# M705X.net
KiCad netlist of a schematic drawn in EAGLE
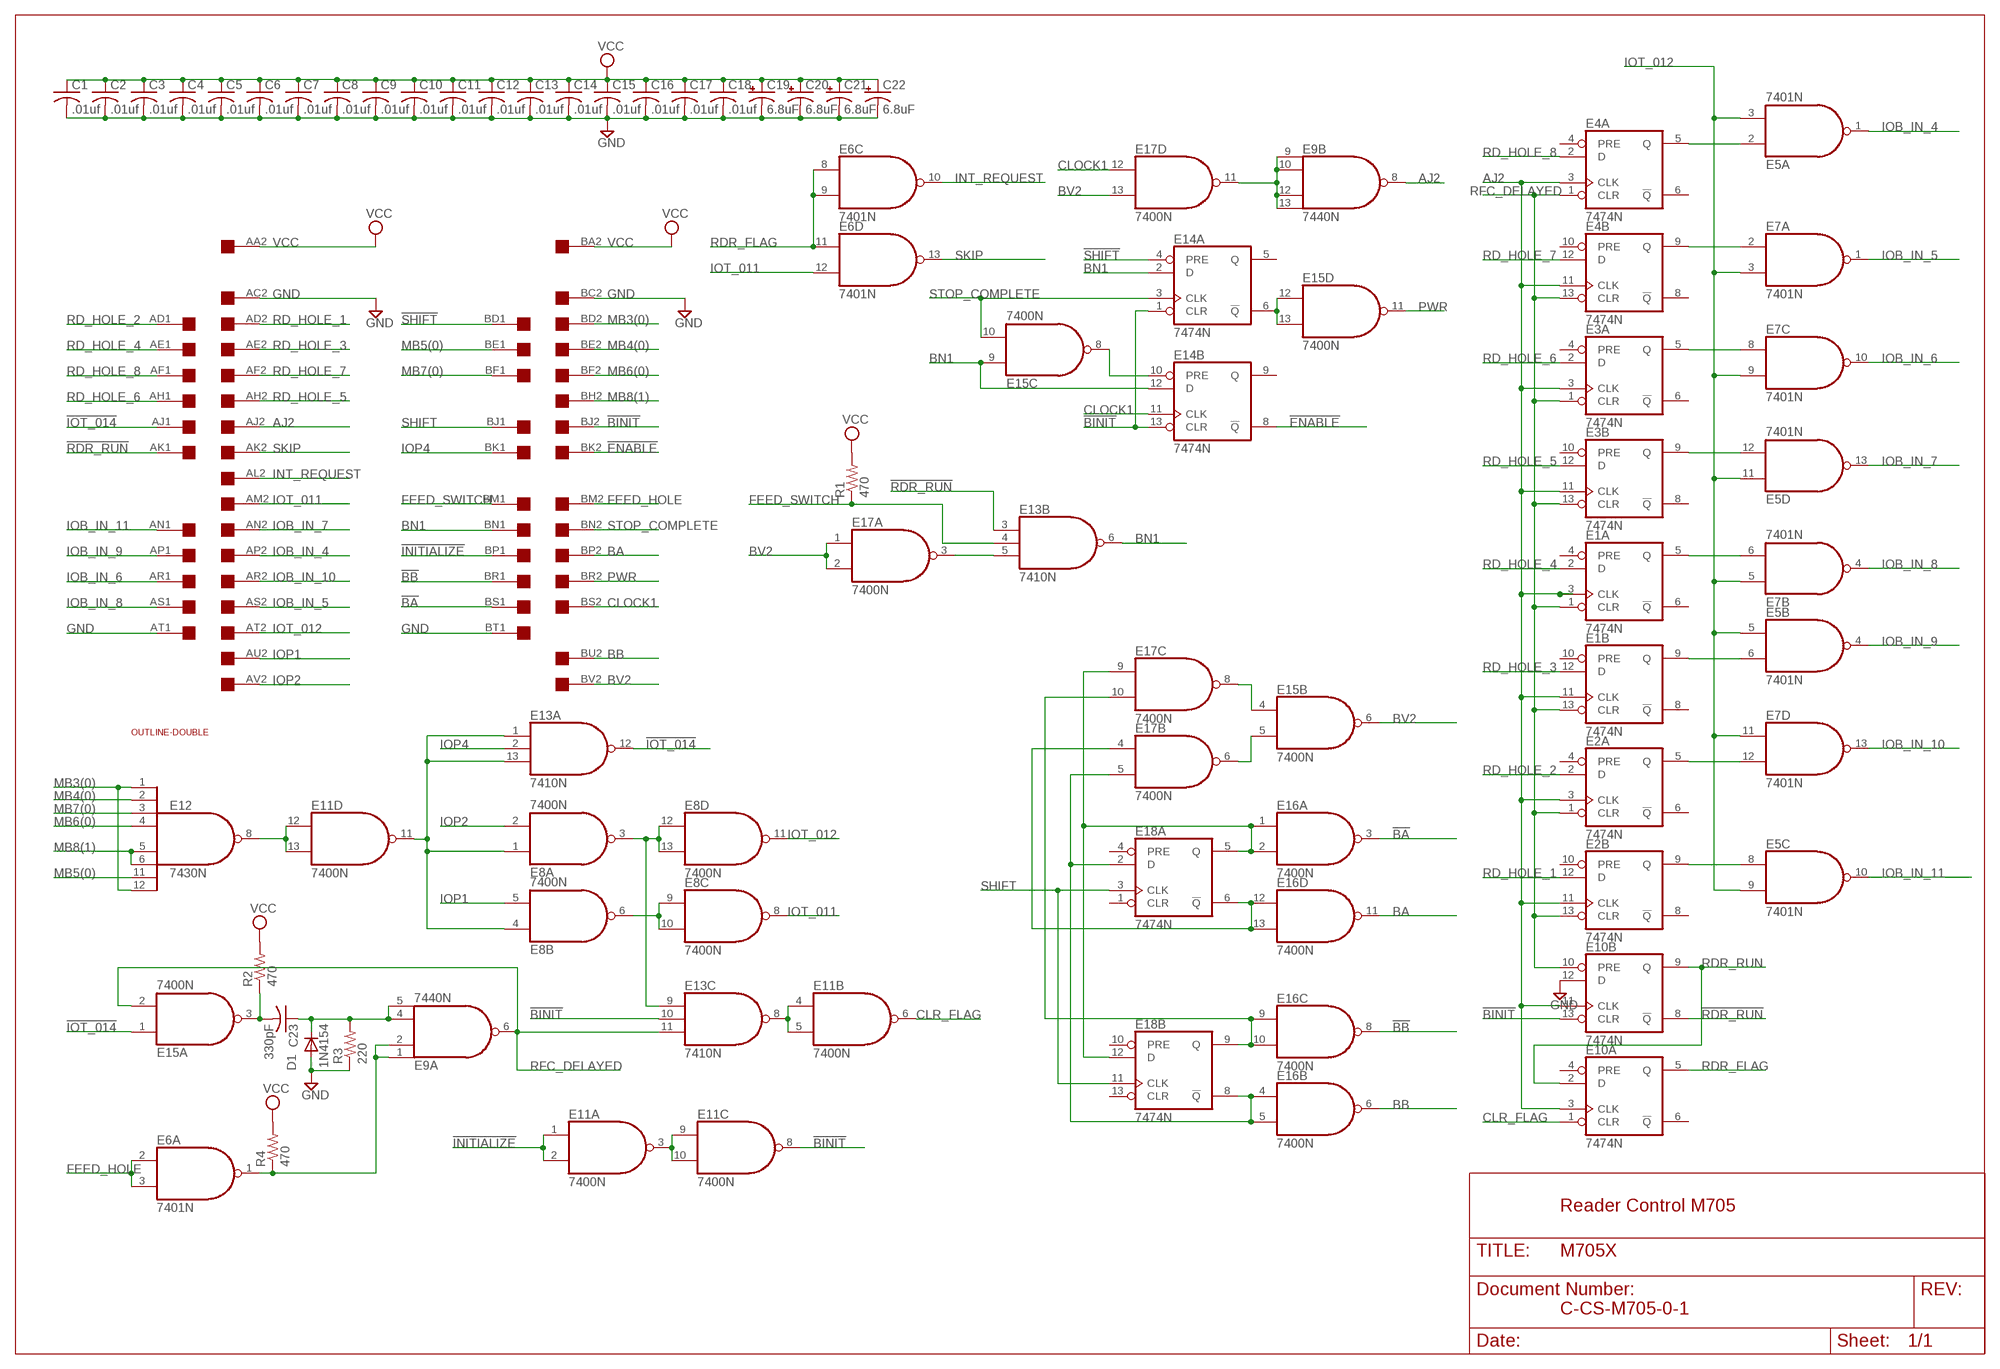
[diagram p0: schematic, sheet 1]

(export (version "E")
  (design (tool "Eeschema 10.0.6"))
  (components
    (comp (ref "C1")
      (value ".01uf")
      (footprint "eagle-import:C075-032X103")
      (libsource (lib "eagle-import") (part "C-US075-032X103"))
    )
    (comp (ref "C2")
      (value ".01uf")
      (footprint "eagle-import:C075-032X103")
      (libsource (lib "eagle-import") (part "C-US075-032X103"))
    )
    (comp (ref "C3")
      (value ".01uf")
      (footprint "eagle-import:C075-032X103")
      (libsource (lib "eagle-import") (part "C-US075-032X103"))
    )
    (comp (ref "C4")
      (value ".01uf")
      (footprint "eagle-import:C075-032X103")
      (libsource (lib "eagle-import") (part "C-US075-032X103"))
    )
    (comp (ref "C5")
      (value ".01uf")
      (footprint "eagle-import:C075-032X103")
      (libsource (lib "eagle-import") (part "C-US075-032X103"))
    )
    (comp (ref "C6")
      (value ".01uf")
      (footprint "eagle-import:C075-032X103")
      (libsource (lib "eagle-import") (part "C-US075-032X103"))
    )
    (comp (ref "C7")
      (value ".01uf")
      (footprint "eagle-import:C075-032X103")
      (libsource (lib "eagle-import") (part "C-US075-032X103"))
    )
    (comp (ref "C8")
      (value ".01uf")
      (footprint "eagle-import:C075-032X103")
      (libsource (lib "eagle-import") (part "C-US075-032X103"))
    )
    (comp (ref "C9")
      (value ".01uf")
      (footprint "eagle-import:C075-032X103")
      (libsource (lib "eagle-import") (part "C-US075-032X103"))
    )
    (comp (ref "C10")
      (value ".01uf")
      (footprint "eagle-import:C075-032X103")
      (libsource (lib "eagle-import") (part "C-US075-032X103"))
    )
    (comp (ref "C11")
      (value ".01uf")
      (footprint "eagle-import:C075-032X103")
      (libsource (lib "eagle-import") (part "C-US075-032X103"))
    )
    (comp (ref "C12")
      (value ".01uf")
      (footprint "eagle-import:C075-032X103")
      (libsource (lib "eagle-import") (part "C-US075-032X103"))
    )
    (comp (ref "C13")
      (value ".01uf")
      (footprint "eagle-import:C075-032X103")
      (libsource (lib "eagle-import") (part "C-US075-032X103"))
    )
    (comp (ref "C14")
      (value ".01uf")
      (footprint "eagle-import:C075-032X103")
      (libsource (lib "eagle-import") (part "C-US075-032X103"))
    )
    (comp (ref "C15")
      (value ".01uf")
      (footprint "eagle-import:C075-032X103")
      (libsource (lib "eagle-import") (part "C-US075-032X103"))
    )
    (comp (ref "C16")
      (value ".01uf")
      (footprint "eagle-import:C075-032X103")
      (libsource (lib "eagle-import") (part "C-US075-032X103"))
    )
    (comp (ref "C17")
      (value ".01uf")
      (footprint "eagle-import:C075-032X103")
      (libsource (lib "eagle-import") (part "C-US075-032X103"))
    )
    (comp (ref "C18")
      (value ".01uf")
      (footprint "eagle-import:C075-032X103")
      (libsource (lib "eagle-import") (part "C-US075-032X103"))
    )
    (comp (ref "C19")
      (value "6.8uF")
      (footprint "eagle-import:E12-8")
      (libsource (lib "eagle-import") (part "CPOL-USE20-8AXIAL"))
    )
    (comp (ref "C20")
      (value "6.8uF")
      (footprint "eagle-import:E12-8")
      (libsource (lib "eagle-import") (part "CPOL-USE20-8AXIAL"))
    )
    (comp (ref "C21")
      (value "6.8uF")
      (footprint "eagle-import:E12-8")
      (libsource (lib "eagle-import") (part "CPOL-USE20-8AXIAL"))
    )
    (comp (ref "C22")
      (value "6.8uF")
      (footprint "eagle-import:E12-8")
      (libsource (lib "eagle-import") (part "CPOL-USE20-8AXIAL"))
    )
    (comp (ref "C23")
      (value "330pF")
      (footprint "eagle-import:C075-032X103")
      (libsource (lib "eagle-import") (part "C-US075-032X103"))
    )
    (comp (ref "D1")
      (value "1N4154")
      (footprint "eagle-import:DO35-10")
      (libsource (lib "eagle-import") (part "1N4148DO35-10"))
    )
    (comp (ref "E1")
      (value "7474N")
      (footprint "eagle-import:DIL14")
      (libsource (lib "eagle-import") (part "7474NS"))
    )
    (comp (ref "E2")
      (value "7474N")
      (footprint "eagle-import:DIL14")
      (libsource (lib "eagle-import") (part "7474NS"))
    )
    (comp (ref "E3")
      (value "7474N")
      (footprint "eagle-import:DIL14")
      (libsource (lib "eagle-import") (part "7474NS"))
    )
    (comp (ref "E4")
      (value "7474N")
      (footprint "eagle-import:DIL14")
      (libsource (lib "eagle-import") (part "7474NS"))
    )
    (comp (ref "E5")
      (value "7401N")
      (footprint "eagle-import:DIL14")
      (libsource (lib "eagle-import") (part "7401NLS"))
    )
    (comp (ref "E6")
      (value "7401N")
      (footprint "eagle-import:DIL14")
      (libsource (lib "eagle-import") (part "7401NLS"))
    )
    (comp (ref "E7")
      (value "7401N")
      (footprint "eagle-import:DIL14")
      (libsource (lib "eagle-import") (part "7401NLS"))
    )
    (comp (ref "E8")
      (value "7400N")
      (footprint "eagle-import:DIL14")
      (libsource (lib "eagle-import") (part "7400N"))
    )
    (comp (ref "E9")
      (value "7440N")
      (footprint "eagle-import:DIL14")
      (libsource (lib "eagle-import") (part "7420NS"))
    )
    (comp (ref "E10")
      (value "7474N")
      (footprint "eagle-import:DIL14")
      (libsource (lib "eagle-import") (part "7474NS"))
    )
    (comp (ref "E11")
      (value "7400N")
      (footprint "eagle-import:DIL14")
      (libsource (lib "eagle-import") (part "7400N"))
    )
    (comp (ref "E12")
      (value "7430N")
      (footprint "eagle-import:DIL14")
      (libsource (lib "eagle-import") (part "7430N"))
    )
    (comp (ref "E13")
      (value "7410N")
      (footprint "eagle-import:DIL14")
      (libsource (lib "eagle-import") (part "7410N"))
    )
    (comp (ref "E14")
      (value "7474N")
      (footprint "eagle-import:DIL14")
      (libsource (lib "eagle-import") (part "7474NS"))
    )
    (comp (ref "E15")
      (value "7400N")
      (footprint "eagle-import:DIL14")
      (libsource (lib "eagle-import") (part "7400N"))
    )
    (comp (ref "E16")
      (value "7400N")
      (footprint "eagle-import:DIL14")
      (libsource (lib "eagle-import") (part "7400N"))
    )
    (comp (ref "E17")
      (value "7400N")
      (footprint "eagle-import:DIL14")
      (libsource (lib "eagle-import") (part "7400N"))
    )
    (comp (ref "E18")
      (value "7474N")
      (footprint "eagle-import:DIL14")
      (libsource (lib "eagle-import") (part "7474NS"))
    )
    (comp (ref "R1")
      (value "470")
      (footprint "eagle-import:0207_10")
      (libsource (lib "eagle-import") (part "R-US_0207/10"))
    )
    (comp (ref "R2")
      (value "470")
      (footprint "eagle-import:0207_10")
      (libsource (lib "eagle-import") (part "R-US_0207/10"))
    )
    (comp (ref "R3")
      (value "220")
      (footprint "eagle-import:0207_10")
      (libsource (lib "eagle-import") (part "R-US_0207/10"))
    )
    (comp (ref "R4")
      (value "470")
      (footprint "eagle-import:0207_10")
      (libsource (lib "eagle-import") (part "R-US_0207/10"))
    )
    (comp (ref "U$5")
      (value "DOUBLE")
      (footprint "eagle-import:EDGE-CON4")
      (libsource (lib "eagle-import") (part "DOUBLE"))
    )
    (comp (ref "U$6")
      (value "OUTLINE-DOUBLE")
      (footprint "eagle-import:DOUBLE")
      (libsource (lib "eagle-import") (part "OUTLINE-DOUBLE"))
    )
  )
  (nets
    (net (code "1") (name "/AJ2") (class "Default")
      (node (ref "E1") (pin "11") (pinfunction "CLK_11") (pintype "input"))
      (node (ref "E1") (pin "3") (pinfunction "CLK_3") (pintype "input"))
      (node (ref "E10") (pin "11") (pinfunction "CLK_11") (pintype "input"))
      (node (ref "E10") (pin "3") (pinfunction "CLK_3") (pintype "input"))
      (node (ref "E2") (pin "11") (pinfunction "CLK_11") (pintype "input"))
      (node (ref "E2") (pin "3") (pinfunction "CLK_3") (pintype "input"))
      (node (ref "E3") (pin "11") (pinfunction "CLK_11") (pintype "input"))
      (node (ref "E3") (pin "3") (pinfunction "CLK_3") (pintype "input"))
      (node (ref "E4") (pin "11") (pinfunction "CLK_11") (pintype "input"))
      (node (ref "E4") (pin "3") (pinfunction "CLK_3") (pintype "input"))
      (node (ref "E9") (pin "8") (pinfunction "O_8") (pintype "output"))
      (node (ref "U$5") (pin "AJ2") (pinfunction "1_AJ2") (pintype "bidirectional"))
    )
    (net (code "2") (name "/BA") (class "Default")
      (node (ref "E16") (pin "11") (pinfunction "O_11") (pintype "output"))
      (node (ref "U$5") (pin "BP2") (pinfunction "1_BP2") (pintype "bidirectional"))
    )
    (net (code "3") (name "/BB") (class "Default")
      (node (ref "E16") (pin "6") (pinfunction "O_6") (pintype "output"))
      (node (ref "U$5") (pin "BU2") (pinfunction "1_BU2") (pintype "bidirectional"))
    )
    (net (code "4") (name "/BN1") (class "Default")
      (node (ref "E13") (pin "6") (pinfunction "O_6") (pintype "output"))
      (node (ref "E14") (pin "12") (pinfunction "D_12") (pintype "input"))
      (node (ref "E14") (pin "2") (pinfunction "D_2") (pintype "input"))
      (node (ref "E15") (pin "9") (pinfunction "I0_9") (pintype "input"))
      (node (ref "U$5") (pin "BN1") (pinfunction "1_BN1") (pintype "bidirectional"))
    )
    (net (code "5") (name "/BV2") (class "Default")
      (node (ref "E15") (pin "6") (pinfunction "O_6") (pintype "output"))
      (node (ref "E17") (pin "1") (pinfunction "I0_1") (pintype "input"))
      (node (ref "E17") (pin "13") (pinfunction "I1_13") (pintype "input"))
      (node (ref "E17") (pin "2") (pinfunction "I1_2") (pintype "input"))
      (node (ref "U$5") (pin "BV2") (pinfunction "1_BV2") (pintype "bidirectional"))
    )
    (net (code "6") (name "/CLOCK1") (class "Default")
      (node (ref "E14") (pin "11") (pinfunction "CLK_11") (pintype "input"))
      (node (ref "E17") (pin "12") (pinfunction "I0_12") (pintype "input"))
      (node (ref "U$5") (pin "BS2") (pinfunction "1_BS2") (pintype "bidirectional"))
    )
    (net (code "7") (name "/CLR_FLAG") (class "Default")
      (node (ref "E10") (pin "1") (pinfunction "CLR_1") (pintype "input"))
      (node (ref "E11") (pin "6") (pinfunction "O_6") (pintype "output"))
    )
    (net (code "8") (name "/FEED_HOLE") (class "Default")
      (node (ref "E6") (pin "2") (pinfunction "I0_2") (pintype "input"))
      (node (ref "E6") (pin "3") (pinfunction "I1_3") (pintype "input"))
      (node (ref "U$5") (pin "BM2") (pinfunction "1_BM2") (pintype "bidirectional"))
    )
    (net (code "9") (name "/FEED_SWITCH") (class "Default")
      (node (ref "E13") (pin "4") (pinfunction "I1_4") (pintype "input"))
      (node (ref "R1") (pin "1") (pinfunction "1_1") (pintype "passive"))
      (node (ref "U$5") (pin "BM1") (pinfunction "1_BM1") (pintype "bidirectional"))
    )
    (net (code "10") (name "/INT_REQUEST") (class "Default")
      (node (ref "E6") (pin "10") (pinfunction "O_10") (pintype "open_collector"))
      (node (ref "U$5") (pin "AL2") (pinfunction "1_AL2") (pintype "bidirectional"))
    )
    (net (code "11") (name "/IOB_IN_4") (class "Default")
      (node (ref "E5") (pin "1") (pinfunction "O_1") (pintype "open_collector"))
      (node (ref "U$5") (pin "AP2") (pinfunction "1_AP2") (pintype "bidirectional"))
    )
    (net (code "12") (name "/IOB_IN_5") (class "Default")
      (node (ref "E7") (pin "1") (pinfunction "O_1") (pintype "open_collector"))
      (node (ref "U$5") (pin "AS2") (pinfunction "1_AS2") (pintype "bidirectional"))
    )
    (net (code "13") (name "/IOB_IN_6") (class "Default")
      (node (ref "E7") (pin "10") (pinfunction "O_10") (pintype "open_collector"))
      (node (ref "U$5") (pin "AR1") (pinfunction "1_AR1") (pintype "bidirectional"))
    )
    (net (code "14") (name "/IOB_IN_7") (class "Default")
      (node (ref "E5") (pin "13") (pinfunction "O_13") (pintype "open_collector"))
      (node (ref "U$5") (pin "AN2") (pinfunction "1_AN2") (pintype "bidirectional"))
    )
    (net (code "15") (name "/IOB_IN_8") (class "Default")
      (node (ref "E7") (pin "4") (pinfunction "O_4") (pintype "open_collector"))
      (node (ref "U$5") (pin "AS1") (pinfunction "1_AS1") (pintype "bidirectional"))
    )
    (net (code "16") (name "/IOB_IN_9") (class "Default")
      (node (ref "E5") (pin "4") (pinfunction "O_4") (pintype "open_collector"))
      (node (ref "U$5") (pin "AP1") (pinfunction "1_AP1") (pintype "bidirectional"))
    )
    (net (code "17") (name "/IOB_IN_10") (class "Default")
      (node (ref "E7") (pin "13") (pinfunction "O_13") (pintype "open_collector"))
      (node (ref "U$5") (pin "AR2") (pinfunction "1_AR2") (pintype "bidirectional"))
    )
    (net (code "18") (name "/IOB_IN_11") (class "Default")
      (node (ref "E5") (pin "10") (pinfunction "O_10") (pintype "open_collector"))
      (node (ref "U$5") (pin "AN1") (pinfunction "1_AN1") (pintype "bidirectional"))
    )
    (net (code "19") (name "/IOP1") (class "Default")
      (node (ref "E8") (pin "5") (pinfunction "I1_5") (pintype "input"))
      (node (ref "U$5") (pin "AU2") (pinfunction "1_AU2") (pintype "bidirectional"))
    )
    (net (code "20") (name "/IOP2") (class "Default")
      (node (ref "E8") (pin "2") (pinfunction "I1_2") (pintype "input"))
      (node (ref "U$5") (pin "AV2") (pinfunction "1_AV2") (pintype "bidirectional"))
    )
    (net (code "21") (name "/IOP4") (class "Default")
      (node (ref "E13") (pin "2") (pinfunction "I1_2") (pintype "input"))
      (node (ref "U$5") (pin "BK1") (pinfunction "1_BK1") (pintype "bidirectional"))
    )
    (net (code "22") (name "/IOT_011") (class "Default")
      (node (ref "E6") (pin "12") (pinfunction "I1_12") (pintype "input"))
      (node (ref "E8") (pin "8") (pinfunction "O_8") (pintype "output"))
      (node (ref "U$5") (pin "AM2") (pinfunction "1_AM2") (pintype "bidirectional"))
    )
    (net (code "23") (name "/IOT_012") (class "Default")
      (node (ref "E5") (pin "11") (pinfunction "I0_11") (pintype "input"))
      (node (ref "E5") (pin "3") (pinfunction "I1_3") (pintype "input"))
      (node (ref "E5") (pin "5") (pinfunction "I0_5") (pintype "input"))
      (node (ref "E5") (pin "9") (pinfunction "I1_9") (pintype "input"))
      (node (ref "E7") (pin "11") (pinfunction "I0_11") (pintype "input"))
      (node (ref "E7") (pin "3") (pinfunction "I1_3") (pintype "input"))
      (node (ref "E7") (pin "5") (pinfunction "I0_5") (pintype "input"))
      (node (ref "E7") (pin "9") (pinfunction "I1_9") (pintype "input"))
      (node (ref "E8") (pin "11") (pinfunction "O_11") (pintype "output"))
      (node (ref "U$5") (pin "AT2") (pinfunction "1_AT2") (pintype "bidirectional"))
    )
    (net (code "24") (name "/MB3(0)") (class "Default")
      (node (ref "E12") (pin "1") (pinfunction "I0_1") (pintype "input"))
      (node (ref "E12") (pin "12") (pinfunction "I7_12") (pintype "input"))
      (node (ref "U$5") (pin "BD2") (pinfunction "1_BD2") (pintype "bidirectional"))
    )
    (net (code "25") (name "/MB4(0)") (class "Default")
      (node (ref "E12") (pin "2") (pinfunction "I1_2") (pintype "input"))
      (node (ref "U$5") (pin "BE2") (pinfunction "1_BE2") (pintype "bidirectional"))
    )
    (net (code "26") (name "/MB5(0)") (class "Default")
      (node (ref "E12") (pin "11") (pinfunction "I6_11") (pintype "input"))
      (node (ref "U$5") (pin "BE1") (pinfunction "1_BE1") (pintype "bidirectional"))
    )
    (net (code "27") (name "/MB6(0)") (class "Default")
      (node (ref "E12") (pin "4") (pinfunction "I3_4") (pintype "input"))
      (node (ref "U$5") (pin "BF2") (pinfunction "1_BF2") (pintype "bidirectional"))
    )
    (net (code "28") (name "/MB7(0)") (class "Default")
      (node (ref "E12") (pin "3") (pinfunction "I2_3") (pintype "input"))
      (node (ref "U$5") (pin "BF1") (pinfunction "1_BF1") (pintype "bidirectional"))
    )
    (net (code "29") (name "/MB8(1)") (class "Default")
      (node (ref "E12") (pin "5") (pinfunction "I4_5") (pintype "input"))
      (node (ref "E12") (pin "6") (pinfunction "I5_6") (pintype "input"))
      (node (ref "U$5") (pin "BH2") (pinfunction "1_BH2") (pintype "bidirectional"))
    )
    (net (code "30") (name "/PWR") (class "Default")
      (node (ref "E15") (pin "11") (pinfunction "O_11") (pintype "output"))
      (node (ref "U$5") (pin "BR2") (pinfunction "1_BR2") (pintype "bidirectional"))
    )
    (net (code "31") (name "/RDR_FLAG") (class "Default")
      (node (ref "E10") (pin "5") (pinfunction "Q_5") (pintype "output"))
      (node (ref "E6") (pin "11") (pinfunction "I0_11") (pintype "input"))
      (node (ref "E6") (pin "8") (pinfunction "I0_8") (pintype "input"))
      (node (ref "E6") (pin "9") (pinfunction "I1_9") (pintype "input"))
    )
    (net (code "32") (name "/RDR_RUN") (class "Default")
      (node (ref "E10") (pin "2") (pinfunction "D_2") (pintype "input"))
      (node (ref "E10") (pin "9") (pinfunction "Q_9") (pintype "output"))
    )
    (net (code "33") (name "/RD_HOLE_1") (class "Default")
      (node (ref "E2") (pin "12") (pinfunction "D_12") (pintype "input"))
      (node (ref "U$5") (pin "AD2") (pinfunction "1_AD2") (pintype "bidirectional"))
    )
    (net (code "34") (name "/RD_HOLE_2") (class "Default")
      (node (ref "E2") (pin "2") (pinfunction "D_2") (pintype "input"))
      (node (ref "U$5") (pin "AD1") (pinfunction "1_AD1") (pintype "bidirectional"))
    )
    (net (code "35") (name "/RD_HOLE_3") (class "Default")
      (node (ref "E1") (pin "12") (pinfunction "D_12") (pintype "input"))
      (node (ref "U$5") (pin "AE2") (pinfunction "1_AE2") (pintype "bidirectional"))
    )
    (net (code "36") (name "/RD_HOLE_4") (class "Default")
      (node (ref "E1") (pin "2") (pinfunction "D_2") (pintype "input"))
      (node (ref "U$5") (pin "AE1") (pinfunction "1_AE1") (pintype "bidirectional"))
    )
    (net (code "37") (name "/RD_HOLE_5") (class "Default")
      (node (ref "E3") (pin "12") (pinfunction "D_12") (pintype "input"))
      (node (ref "U$5") (pin "AH2") (pinfunction "1_AH2") (pintype "bidirectional"))
    )
    (net (code "38") (name "/RD_HOLE_6") (class "Default")
      (node (ref "E3") (pin "2") (pinfunction "D_2") (pintype "input"))
      (node (ref "U$5") (pin "AH1") (pinfunction "1_AH1") (pintype "bidirectional"))
    )
    (net (code "39") (name "/RD_HOLE_7") (class "Default")
      (node (ref "E4") (pin "12") (pinfunction "D_12") (pintype "input"))
      (node (ref "U$5") (pin "AF2") (pinfunction "1_AF2") (pintype "bidirectional"))
    )
    (net (code "40") (name "/RD_HOLE_8") (class "Default")
      (node (ref "E4") (pin "2") (pinfunction "D_2") (pintype "input"))
      (node (ref "U$5") (pin "AF1") (pinfunction "1_AF1") (pintype "bidirectional"))
    )
    (net (code "41") (name "/RFC_DELAYED") (class "Default")
      (node (ref "E1") (pin "1") (pinfunction "CLR_1") (pintype "input"))
      (node (ref "E1") (pin "13") (pinfunction "CLR_13") (pintype "input"))
      (node (ref "E10") (pin "10") (pinfunction "PRE_10") (pintype "input"))
      (node (ref "E13") (pin "11") (pinfunction "I2_11") (pintype "input"))
      (node (ref "E15") (pin "2") (pinfunction "I1_2") (pintype "input"))
      (node (ref "E2") (pin "1") (pinfunction "CLR_1") (pintype "input"))
      (node (ref "E2") (pin "13") (pinfunction "CLR_13") (pintype "input"))
      (node (ref "E3") (pin "1") (pinfunction "CLR_1") (pintype "input"))
      (node (ref "E3") (pin "13") (pinfunction "CLR_13") (pintype "input"))
      (node (ref "E4") (pin "1") (pinfunction "CLR_1") (pintype "input"))
      (node (ref "E4") (pin "13") (pinfunction "CLR_13") (pintype "input"))
      (node (ref "E9") (pin "6") (pinfunction "O_6") (pintype "output"))
    )
    (net (code "42") (name "/SHIFT") (class "Default")
      (node (ref "E18") (pin "11") (pinfunction "CLK_11") (pintype "input"))
      (node (ref "E18") (pin "3") (pinfunction "CLK_3") (pintype "input"))
      (node (ref "U$5") (pin "BJ1") (pinfunction "1_BJ1") (pintype "bidirectional"))
    )
    (net (code "43") (name "/SKIP") (class "Default")
      (node (ref "E6") (pin "13") (pinfunction "O_13") (pintype "open_collector"))
      (node (ref "U$5") (pin "AK2") (pinfunction "1_AK2") (pintype "bidirectional"))
    )
    (net (code "44") (name "/STOP_COMPLETE") (class "Default")
      (node (ref "E14") (pin "3") (pinfunction "CLK_3") (pintype "input"))
      (node (ref "E15") (pin "10") (pinfunction "I1_10") (pintype "input"))
      (node (ref "U$5") (pin "BN2") (pinfunction "1_BN2") (pintype "bidirectional"))
    )
    (net (code "45") (name "/~{BA}") (class "Default")
      (node (ref "E16") (pin "3") (pinfunction "O_3") (pintype "output"))
      (node (ref "U$5") (pin "BS1") (pinfunction "1_BS1") (pintype "bidirectional"))
    )
    (net (code "46") (name "/~{BB}") (class "Default")
      (node (ref "E16") (pin "8") (pinfunction "O_8") (pintype "output"))
      (node (ref "U$5") (pin "BR1") (pinfunction "1_BR1") (pintype "bidirectional"))
    )
    (net (code "47") (name "/~{BINIT}") (class "Default")
      (node (ref "E10") (pin "13") (pinfunction "CLR_13") (pintype "input"))
      (node (ref "E11") (pin "8") (pinfunction "O_8") (pintype "output"))
      (node (ref "E13") (pin "10") (pinfunction "I1_10") (pintype "input"))
      (node (ref "E14") (pin "1") (pinfunction "CLR_1") (pintype "input"))
      (node (ref "E14") (pin "13") (pinfunction "CLR_13") (pintype "input"))
      (node (ref "U$5") (pin "BJ2") (pinfunction "1_BJ2") (pintype "bidirectional"))
    )
    (net (code "48") (name "/~{ENABLE}") (class "Default")
      (node (ref "E14") (pin "8") (pinfunction "~{Q}_8") (pintype "output"))
      (node (ref "U$5") (pin "BK2") (pinfunction "1_BK2") (pintype "bidirectional"))
    )
    (net (code "49") (name "/~{INITIALIZE}") (class "Default")
      (node (ref "E11") (pin "1") (pinfunction "I0_1") (pintype "input"))
      (node (ref "E11") (pin "2") (pinfunction "I1_2") (pintype "input"))
      (node (ref "U$5") (pin "BP1") (pinfunction "1_BP1") (pintype "bidirectional"))
    )
    (net (code "50") (name "/~{IOT_014}") (class "Default")
      (node (ref "E13") (pin "12") (pinfunction "O_12") (pintype "output"))
      (node (ref "E15") (pin "1") (pinfunction "I0_1") (pintype "input"))
      (node (ref "U$5") (pin "AJ1") (pinfunction "1_AJ1") (pintype "bidirectional"))
    )
    (net (code "51") (name "/~{RDR_RUN}") (class "Default")
      (node (ref "E10") (pin "8") (pinfunction "~{Q}_8") (pintype "output"))
      (node (ref "E13") (pin "3") (pinfunction "I0_3") (pintype "input"))
      (node (ref "U$5") (pin "AK1") (pinfunction "1_AK1") (pintype "bidirectional"))
    )
    (net (code "52") (name "/~{SHIFT}") (class "Default")
      (node (ref "E14") (pin "4") (pinfunction "PRE_4") (pintype "input"))
      (node (ref "U$5") (pin "BD1") (pinfunction "1_BD1") (pintype "bidirectional"))
    )
    (net (code "53") (name "GND") (class "Default")
      (node (ref "C1") (pin "2") (pinfunction "2_2") (pintype "passive"))
      (node (ref "C10") (pin "2") (pinfunction "2_2") (pintype "passive"))
      (node (ref "C11") (pin "2") (pinfunction "2_2") (pintype "passive"))
      (node (ref "C12") (pin "2") (pinfunction "2_2") (pintype "passive"))
      (node (ref "C13") (pin "2") (pinfunction "2_2") (pintype "passive"))
      (node (ref "C14") (pin "2") (pinfunction "2_2") (pintype "passive"))
      (node (ref "C15") (pin "2") (pinfunction "2_2") (pintype "passive"))
      (node (ref "C16") (pin "2") (pinfunction "2_2") (pintype "passive"))
      (node (ref "C17") (pin "2") (pinfunction "2_2") (pintype "passive"))
      (node (ref "C18") (pin "2") (pinfunction "2_2") (pintype "passive"))
      (node (ref "C19") (pin "-") (pinfunction "-_-") (pintype "passive"))
      (node (ref "C2") (pin "2") (pinfunction "2_2") (pintype "passive"))
      (node (ref "C20") (pin "-") (pinfunction "-_-") (pintype "passive"))
      (node (ref "C21") (pin "-") (pinfunction "-_-") (pintype "passive"))
      (node (ref "C22") (pin "-") (pinfunction "-_-") (pintype "passive"))
      (node (ref "C3") (pin "2") (pinfunction "2_2") (pintype "passive"))
      (node (ref "C4") (pin "2") (pinfunction "2_2") (pintype "passive"))
      (node (ref "C5") (pin "2") (pinfunction "2_2") (pintype "passive"))
      (node (ref "C6") (pin "2") (pinfunction "2_2") (pintype "passive"))
      (node (ref "C7") (pin "2") (pinfunction "2_2") (pintype "passive"))
      (node (ref "C8") (pin "2") (pinfunction "2_2") (pintype "passive"))
      (node (ref "C9") (pin "2") (pinfunction "2_2") (pintype "passive"))
      (node (ref "D1") (pin "A") (pinfunction "A_A") (pintype "passive"))
      (node (ref "E10") (pin "12") (pinfunction "D_12") (pintype "input"))
      (node (ref "R3") (pin "1") (pinfunction "1_1") (pintype "passive"))
      (node (ref "U$5") (pin "AC2") (pinfunction "1_AC2") (pintype "bidirectional"))
      (node (ref "U$5") (pin "AT1") (pinfunction "1_AT1") (pintype "bidirectional"))
      (node (ref "U$5") (pin "BC2") (pinfunction "1_BC2") (pintype "bidirectional"))
      (node (ref "U$5") (pin "BT1") (pinfunction "1_BT1") (pintype "bidirectional"))
    )
    (net (code "54") (name "Net-(E1A-Q)") (class "Default")
      (node (ref "E1") (pin "5") (pinfunction "Q_5") (pintype "output"))
      (node (ref "E7") (pin "6") (pinfunction "I1_6") (pintype "input"))
    )
    (net (code "55") (name "Net-(E1B-Q)") (class "Default")
      (node (ref "E1") (pin "9") (pinfunction "Q_9") (pintype "output"))
      (node (ref "E5") (pin "6") (pinfunction "I1_6") (pintype "input"))
    )
    (net (code "56") (name "Net-(E2A-Q)") (class "Default")
      (node (ref "E2") (pin "5") (pinfunction "Q_5") (pintype "output"))
      (node (ref "E7") (pin "12") (pinfunction "I1_12") (pintype "input"))
    )
    (net (code "57") (name "Net-(E2B-Q)") (class "Default")
      (node (ref "E2") (pin "9") (pinfunction "Q_9") (pintype "output"))
      (node (ref "E5") (pin "8") (pinfunction "I0_8") (pintype "input"))
    )
    (net (code "58") (name "Net-(E3A-Q)") (class "Default")
      (node (ref "E3") (pin "5") (pinfunction "Q_5") (pintype "output"))
      (node (ref "E7") (pin "8") (pinfunction "I0_8") (pintype "input"))
    )
    (net (code "59") (name "Net-(E3B-Q)") (class "Default")
      (node (ref "E3") (pin "9") (pinfunction "Q_9") (pintype "output"))
      (node (ref "E5") (pin "12") (pinfunction "I1_12") (pintype "input"))
    )
    (net (code "60") (name "Net-(E4A-Q)") (class "Default")
      (node (ref "E4") (pin "5") (pinfunction "Q_5") (pintype "output"))
      (node (ref "E5") (pin "2") (pinfunction "I0_2") (pintype "input"))
    )
    (net (code "61") (name "Net-(E4B-Q)") (class "Default")
      (node (ref "E4") (pin "9") (pinfunction "Q_9") (pintype "output"))
      (node (ref "E7") (pin "2") (pinfunction "I0_2") (pintype "input"))
    )
    (net (code "62") (name "Net-(E6A-O)") (class "Default")
      (node (ref "E6") (pin "1") (pinfunction "O_1") (pintype "open_collector"))
      (node (ref "E9") (pin "1") (pinfunction "I0_1") (pintype "input"))
      (node (ref "E9") (pin "2") (pinfunction "I1_2") (pintype "input"))
      (node (ref "R4") (pin "1") (pinfunction "1_1") (pintype "passive"))
    )
    (net (code "63") (name "Net-(E8B-O)") (class "Default")
      (node (ref "E8") (pin "10") (pinfunction "I1_10") (pintype "input"))
      (node (ref "E8") (pin "6") (pinfunction "O_6") (pintype "output"))
      (node (ref "E8") (pin "9") (pinfunction "I0_9") (pintype "input"))
    )
    (net (code "64") (name "Net-(E9A-I2)") (class "Default")
      (node (ref "C23") (pin "1") (pinfunction "1_1") (pintype "passive"))
      (node (ref "D1") (pin "C") (pinfunction "C_C") (pintype "passive"))
      (node (ref "E9") (pin "4") (pinfunction "I2_4") (pintype "input"))
      (node (ref "E9") (pin "5") (pinfunction "I3_5") (pintype "input"))
      (node (ref "R3") (pin "2") (pinfunction "2_2") (pintype "passive"))
    )
    (net (code "65") (name "Net-(E11A-O)") (class "Default")
      (node (ref "E11") (pin "10") (pinfunction "I1_10") (pintype "input"))
      (node (ref "E11") (pin "3") (pinfunction "O_3") (pintype "output"))
      (node (ref "E11") (pin "9") (pinfunction "I0_9") (pintype "input"))
    )
    (net (code "66") (name "Net-(E11B-I0)") (class "Default")
      (node (ref "E11") (pin "4") (pinfunction "I0_4") (pintype "input"))
      (node (ref "E11") (pin "5") (pinfunction "I1_5") (pintype "input"))
      (node (ref "E13") (pin "8") (pinfunction "O_8") (pintype "output"))
    )
    (net (code "67") (name "Net-(E11D-I0)") (class "Default")
      (node (ref "E11") (pin "12") (pinfunction "I0_12") (pintype "input"))
      (node (ref "E11") (pin "13") (pinfunction "I1_13") (pintype "input"))
      (node (ref "E12") (pin "8") (pinfunction "O_8") (pintype "output"))
    )
    (net (code "68") (name "Net-(E11D-O)") (class "Default")
      (node (ref "E11") (pin "11") (pinfunction "O_11") (pintype "output"))
      (node (ref "E13") (pin "1") (pinfunction "I0_1") (pintype "input"))
      (node (ref "E13") (pin "13") (pinfunction "I2_13") (pintype "input"))
      (node (ref "E8") (pin "1") (pinfunction "I0_1") (pintype "input"))
      (node (ref "E8") (pin "4") (pinfunction "I0_4") (pintype "input"))
    )
    (net (code "69") (name "Net-(E13B-I2)") (class "Default")
      (node (ref "E13") (pin "5") (pinfunction "I2_5") (pintype "input"))
      (node (ref "E17") (pin "3") (pinfunction "O_3") (pintype "output"))
    )
    (net (code "70") (name "Net-(E13C-I0)") (class "Default")
      (node (ref "E13") (pin "9") (pinfunction "I0_9") (pintype "input"))
      (node (ref "E8") (pin "12") (pinfunction "I0_12") (pintype "input"))
      (node (ref "E8") (pin "13") (pinfunction "I1_13") (pintype "input"))
      (node (ref "E8") (pin "3") (pinfunction "O_3") (pintype "output"))
    )
    (net (code "71") (name "Net-(E14A-~{Q})") (class "Default")
      (node (ref "E14") (pin "6") (pinfunction "~{Q}_6") (pintype "output"))
      (node (ref "E15") (pin "12") (pinfunction "I0_12") (pintype "input"))
      (node (ref "E15") (pin "13") (pinfunction "I1_13") (pintype "input"))
    )
    (net (code "72") (name "Net-(E14B-PRE)") (class "Default")
      (node (ref "E14") (pin "10") (pinfunction "PRE_10") (pintype "input"))
      (node (ref "E15") (pin "8") (pinfunction "O_8") (pintype "output"))
    )
    (net (code "73") (name "Net-(E15A-O)") (class "Default")
      (node (ref "C23") (pin "2") (pinfunction "2_2") (pintype "passive"))
      (node (ref "E15") (pin "3") (pinfunction "O_3") (pintype "output"))
      (node (ref "R2") (pin "1") (pinfunction "1_1") (pintype "passive"))
    )
    (net (code "74") (name "Net-(E15B-I0)") (class "Default")
      (node (ref "E15") (pin "4") (pinfunction "I0_4") (pintype "input"))
      (node (ref "E17") (pin "8") (pinfunction "O_8") (pintype "output"))
    )
    (net (code "75") (name "Net-(E15B-I1)") (class "Default")
      (node (ref "E15") (pin "5") (pinfunction "I1_5") (pintype "input"))
      (node (ref "E17") (pin "6") (pinfunction "O_6") (pintype "output"))
    )
    (net (code "76") (name "Net-(E16A-I0)") (class "Default")
      (node (ref "E16") (pin "1") (pinfunction "I0_1") (pintype "input"))
      (node (ref "E16") (pin "2") (pinfunction "I1_2") (pintype "input"))
      (node (ref "E17") (pin "9") (pinfunction "I0_9") (pintype "input"))
      (node (ref "E18") (pin "12") (pinfunction "D_12") (pintype "input"))
      (node (ref "E18") (pin "5") (pinfunction "Q_5") (pintype "output"))
    )
    (net (code "77") (name "Net-(E16B-I0)") (class "Default")
      (node (ref "E16") (pin "4") (pinfunction "I0_4") (pintype "input"))
      (node (ref "E16") (pin "5") (pinfunction "I1_5") (pintype "input"))
      (node (ref "E17") (pin "5") (pinfunction "I1_5") (pintype "input"))
      (node (ref "E18") (pin "2") (pinfunction "D_2") (pintype "input"))
      (node (ref "E18") (pin "8") (pinfunction "~{Q}_8") (pintype "output"))
    )
    (net (code "78") (name "Net-(E16C-I0)") (class "Default")
      (node (ref "E16") (pin "10") (pinfunction "I1_10") (pintype "input"))
      (node (ref "E16") (pin "9") (pinfunction "I0_9") (pintype "input"))
      (node (ref "E17") (pin "10") (pinfunction "I1_10") (pintype "input"))
      (node (ref "E18") (pin "9") (pinfunction "Q_9") (pintype "output"))
    )
    (net (code "79") (name "Net-(E16D-I0)") (class "Default")
      (node (ref "E16") (pin "12") (pinfunction "I0_12") (pintype "input"))
      (node (ref "E16") (pin "13") (pinfunction "I1_13") (pintype "input"))
      (node (ref "E17") (pin "4") (pinfunction "I0_4") (pintype "input"))
      (node (ref "E18") (pin "6") (pinfunction "~{Q}_6") (pintype "output"))
    )
    (net (code "80") (name "Net-(E17D-O)") (class "Default")
      (node (ref "E17") (pin "11") (pinfunction "O_11") (pintype "output"))
      (node (ref "E9") (pin "10") (pinfunction "I1_10") (pintype "input"))
      (node (ref "E9") (pin "12") (pinfunction "I2_12") (pintype "input"))
      (node (ref "E9") (pin "13") (pinfunction "I3_13") (pintype "input"))
      (node (ref "E9") (pin "9") (pinfunction "I0_9") (pintype "input"))
    )
    (net (code "81") (name "VCC") (class "Default")
      (node (ref "C1") (pin "1") (pinfunction "1_1") (pintype "passive"))
      (node (ref "C10") (pin "1") (pinfunction "1_1") (pintype "passive"))
      (node (ref "C11") (pin "1") (pinfunction "1_1") (pintype "passive"))
      (node (ref "C12") (pin "1") (pinfunction "1_1") (pintype "passive"))
      (node (ref "C13") (pin "1") (pinfunction "1_1") (pintype "passive"))
      (node (ref "C14") (pin "1") (pinfunction "1_1") (pintype "passive"))
      (node (ref "C15") (pin "1") (pinfunction "1_1") (pintype "passive"))
      (node (ref "C16") (pin "1") (pinfunction "1_1") (pintype "passive"))
      (node (ref "C17") (pin "1") (pinfunction "1_1") (pintype "passive"))
      (node (ref "C18") (pin "1") (pinfunction "1_1") (pintype "passive"))
      (node (ref "C19") (pin "+") (pinfunction "+_+") (pintype "passive"))
      (node (ref "C2") (pin "1") (pinfunction "1_1") (pintype "passive"))
      (node (ref "C20") (pin "+") (pinfunction "+_+") (pintype "passive"))
      (node (ref "C21") (pin "+") (pinfunction "+_+") (pintype "passive"))
      (node (ref "C22") (pin "+") (pinfunction "+_+") (pintype "passive"))
      (node (ref "C3") (pin "1") (pinfunction "1_1") (pintype "passive"))
      (node (ref "C4") (pin "1") (pinfunction "1_1") (pintype "passive"))
      (node (ref "C5") (pin "1") (pinfunction "1_1") (pintype "passive"))
      (node (ref "C6") (pin "1") (pinfunction "1_1") (pintype "passive"))
      (node (ref "C7") (pin "1") (pinfunction "1_1") (pintype "passive"))
      (node (ref "C8") (pin "1") (pinfunction "1_1") (pintype "passive"))
      (node (ref "C9") (pin "1") (pinfunction "1_1") (pintype "passive"))
      (node (ref "R1") (pin "2") (pinfunction "2_2") (pintype "passive"))
      (node (ref "R2") (pin "2") (pinfunction "2_2") (pintype "passive"))
      (node (ref "R4") (pin "2") (pinfunction "2_2") (pintype "passive"))
      (node (ref "U$5") (pin "AA2") (pinfunction "1_AA2") (pintype "bidirectional"))
      (node (ref "U$5") (pin "BA2") (pinfunction "1_BA2") (pintype "bidirectional"))
    )
    (net (code "82") (name "unconnected-(E1A-PRE-Pad4)") (class "Default")
      (node (ref "E1") (pin "4") (pinfunction "PRE_4") (pintype "input"))
    )
    (net (code "83") (name "unconnected-(E1A-~{Q}-Pad6)") (class "Default")
      (node (ref "E1") (pin "6") (pinfunction "~{Q}_6") (pintype "output"))
    )
    (net (code "84") (name "unconnected-(E1B-PRE-Pad10)") (class "Default")
      (node (ref "E1") (pin "10") (pinfunction "PRE_10") (pintype "input"))
    )
    (net (code "85") (name "unconnected-(E1B-~{Q}-Pad8)") (class "Default")
      (node (ref "E1") (pin "8") (pinfunction "~{Q}_8") (pintype "output"))
    )
    (net (code "86") (name "unconnected-(E2A-PRE-Pad4)") (class "Default")
      (node (ref "E2") (pin "4") (pinfunction "PRE_4") (pintype "input"))
    )
    (net (code "87") (name "unconnected-(E2A-~{Q}-Pad6)") (class "Default")
      (node (ref "E2") (pin "6") (pinfunction "~{Q}_6") (pintype "output"))
    )
    (net (code "88") (name "unconnected-(E2B-PRE-Pad10)") (class "Default")
      (node (ref "E2") (pin "10") (pinfunction "PRE_10") (pintype "input"))
    )
    (net (code "89") (name "unconnected-(E2B-~{Q}-Pad8)") (class "Default")
      (node (ref "E2") (pin "8") (pinfunction "~{Q}_8") (pintype "output"))
    )
    (net (code "90") (name "unconnected-(E3A-PRE-Pad4)") (class "Default")
      (node (ref "E3") (pin "4") (pinfunction "PRE_4") (pintype "input"))
    )
    (net (code "91") (name "unconnected-(E3A-~{Q}-Pad6)") (class "Default")
      (node (ref "E3") (pin "6") (pinfunction "~{Q}_6") (pintype "output"))
    )
    (net (code "92") (name "unconnected-(E3B-PRE-Pad10)") (class "Default")
      (node (ref "E3") (pin "10") (pinfunction "PRE_10") (pintype "input"))
    )
    (net (code "93") (name "unconnected-(E3B-~{Q}-Pad8)") (class "Default")
      (node (ref "E3") (pin "8") (pinfunction "~{Q}_8") (pintype "output"))
    )
    (net (code "94") (name "unconnected-(E4A-PRE-Pad4)") (class "Default")
      (node (ref "E4") (pin "4") (pinfunction "PRE_4") (pintype "input"))
    )
    (net (code "95") (name "unconnected-(E4A-~{Q}-Pad6)") (class "Default")
      (node (ref "E4") (pin "6") (pinfunction "~{Q}_6") (pintype "output"))
    )
    (net (code "96") (name "unconnected-(E4B-PRE-Pad10)") (class "Default")
      (node (ref "E4") (pin "10") (pinfunction "PRE_10") (pintype "input"))
    )
    (net (code "97") (name "unconnected-(E4B-~{Q}-Pad8)") (class "Default")
      (node (ref "E4") (pin "8") (pinfunction "~{Q}_8") (pintype "output"))
    )
    (net (code "98") (name "unconnected-(E10A-PRE-Pad4)") (class "Default")
      (node (ref "E10") (pin "4") (pinfunction "PRE_4") (pintype "input"))
    )
    (net (code "99") (name "unconnected-(E10A-~{Q}-Pad6)") (class "Default")
      (node (ref "E10") (pin "6") (pinfunction "~{Q}_6") (pintype "output"))
    )
    (net (code "100") (name "unconnected-(E14A-Q-Pad5)") (class "Default")
      (node (ref "E14") (pin "5") (pinfunction "Q_5") (pintype "output"))
    )
    (net (code "101") (name "unconnected-(E14B-Q-Pad9)") (class "Default")
      (node (ref "E14") (pin "9") (pinfunction "Q_9") (pintype "output"))
    )
    (net (code "102") (name "unconnected-(E18A-CLR-Pad1)") (class "Default")
      (node (ref "E18") (pin "1") (pinfunction "CLR_1") (pintype "input"))
    )
    (net (code "103") (name "unconnected-(E18A-PRE-Pad4)") (class "Default")
      (node (ref "E18") (pin "4") (pinfunction "PRE_4") (pintype "input"))
    )
    (net (code "104") (name "unconnected-(E18B-CLR-Pad13)") (class "Default")
      (node (ref "E18") (pin "13") (pinfunction "CLR_13") (pintype "input"))
    )
    (net (code "105") (name "unconnected-(E18B-PRE-Pad10)") (class "Default")
      (node (ref "E18") (pin "10") (pinfunction "PRE_10") (pintype "input"))
    )
  )
)
